# Motor_Slave_2.net
KiCad netlist of a schematic drawn in EAGLE
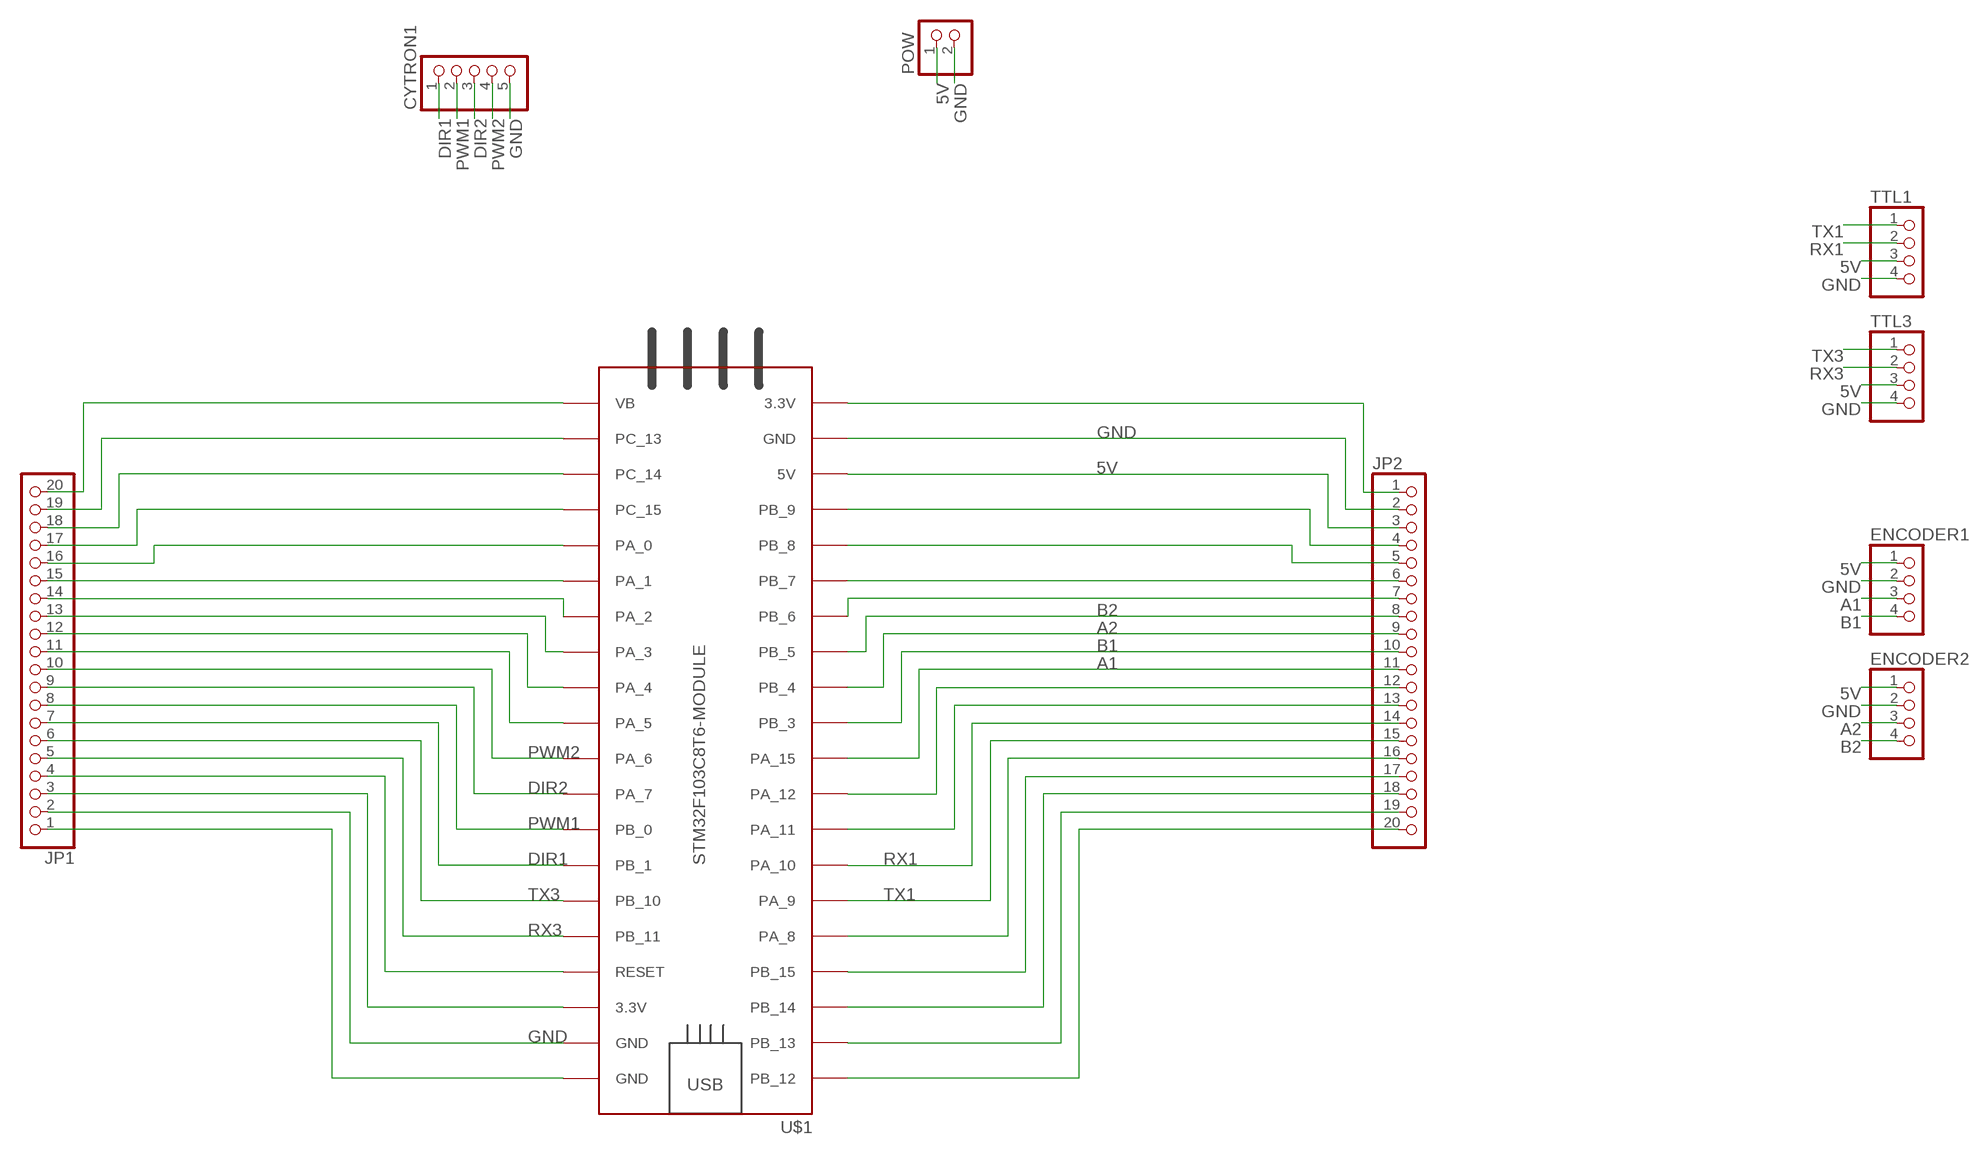
[diagram p0: schematic, sheet 1]

(export (version "E")
  (design (tool "Eeschema 10.0.6"))
  (components
    (comp (ref "CYTRON1")
      (value "PINHD-5_DATA")
      (footprint "eagle-import:1X05_DATA")
      (libsource (lib "eagle-import") (part "PINHD-5_DATA"))
    )
    (comp (ref "ENCODER1")
      (value "PINHD-4_DATA")
      (footprint "eagle-import:1X04_DATA")
      (libsource (lib "eagle-import") (part "PINHD-4_DATA"))
    )
    (comp (ref "ENCODER2")
      (value "PINHD-4_DATA")
      (footprint "eagle-import:1X04_DATA")
      (libsource (lib "eagle-import") (part "PINHD-4_DATA"))
    )
    (comp (ref "JP1")
      (value "PINHD-1X20")
      (footprint "eagle-import:1X20")
      (libsource (lib "eagle-import") (part "PINHD-1X20"))
    )
    (comp (ref "JP2")
      (value "PINHD-1X20")
      (footprint "eagle-import:1X20")
      (libsource (lib "eagle-import") (part "PINHD-1X20"))
    )
    (comp (ref "POW")
      (value "PINHD-2_DATA")
      (footprint "eagle-import:1X02_DATA")
      (libsource (lib "eagle-import") (part "PINHD-2_DATA"))
    )
    (comp (ref "TTL1")
      (value "PINHD-4_DATA")
      (footprint "eagle-import:1X04_DATA")
      (libsource (lib "eagle-import") (part "PINHD-4_DATA"))
    )
    (comp (ref "TTL3")
      (value "PINHD-4_DATA")
      (footprint "eagle-import:1X04_DATA")
      (libsource (lib "eagle-import") (part "PINHD-4_DATA"))
    )
    (comp (ref "U$1")
      (value "STM32F103C8T6-MODULE")
      (footprint "eagle-import:STM32F103C8T6-MODULE")
      (libsource (lib "eagle-import") (part "STM32F103C8T6-MODULE"))
    )
  )
  (nets
    (net (code "1") (name "/5V") (class "Default")
      (node (ref "ENCODER1") (pin "1") (pinfunction "1_1") (pintype "passive"))
      (node (ref "ENCODER2") (pin "1") (pinfunction "1_1") (pintype "passive"))
      (node (ref "JP2") (pin "3") (pinfunction "3_3") (pintype "passive"))
      (node (ref "POW") (pin "1") (pinfunction "1_1") (pintype "passive"))
      (node (ref "TTL1") (pin "3") (pinfunction "3_3") (pintype "passive"))
      (node (ref "TTL3") (pin "3") (pinfunction "3_3") (pintype "passive"))
      (node (ref "U$1") (pin "5V") (pinfunction "5V_5V") (pintype "bidirectional"))
    )
    (net (code "2") (name "/A1") (class "Default")
      (node (ref "ENCODER1") (pin "3") (pinfunction "3_3") (pintype "passive"))
      (node (ref "JP2") (pin "11") (pinfunction "11_11") (pintype "passive"))
      (node (ref "U$1") (pin "PA_15") (pinfunction "PA_15_PA_15") (pintype "bidirectional"))
    )
    (net (code "3") (name "/A2") (class "Default")
      (node (ref "ENCODER2") (pin "3") (pinfunction "3_3") (pintype "passive"))
      (node (ref "JP2") (pin "9") (pinfunction "9_9") (pintype "passive"))
      (node (ref "U$1") (pin "PB_4") (pinfunction "PB_4_PB_4") (pintype "bidirectional"))
    )
    (net (code "4") (name "/B1") (class "Default")
      (node (ref "ENCODER1") (pin "4") (pinfunction "4_4") (pintype "passive"))
      (node (ref "JP2") (pin "10") (pinfunction "10_10") (pintype "passive"))
      (node (ref "U$1") (pin "PB_3") (pinfunction "PB_3_PB_3") (pintype "bidirectional"))
    )
    (net (code "5") (name "/B2") (class "Default")
      (node (ref "ENCODER2") (pin "4") (pinfunction "4_4") (pintype "passive"))
      (node (ref "JP2") (pin "8") (pinfunction "8_8") (pintype "passive"))
      (node (ref "U$1") (pin "PB_5") (pinfunction "PB_5_PB_5") (pintype "bidirectional"))
    )
    (net (code "6") (name "/DIR1") (class "Default")
      (node (ref "CYTRON1") (pin "1") (pinfunction "1_1") (pintype "passive"))
      (node (ref "JP1") (pin "7") (pinfunction "7_7") (pintype "passive"))
      (node (ref "U$1") (pin "PB_1") (pinfunction "PB_1_PB_1") (pintype "bidirectional"))
    )
    (net (code "7") (name "/DIR2") (class "Default")
      (node (ref "CYTRON1") (pin "3") (pinfunction "3_3") (pintype "passive"))
      (node (ref "JP1") (pin "9") (pinfunction "9_9") (pintype "passive"))
      (node (ref "U$1") (pin "PA_7") (pinfunction "PA_7_PA_7") (pintype "bidirectional"))
    )
    (net (code "8") (name "/GND") (class "Default")
      (node (ref "CYTRON1") (pin "5") (pinfunction "5_5") (pintype "passive"))
      (node (ref "ENCODER1") (pin "2") (pinfunction "2_2") (pintype "passive"))
      (node (ref "ENCODER2") (pin "2") (pinfunction "2_2") (pintype "passive"))
      (node (ref "JP1") (pin "2") (pinfunction "2_2") (pintype "passive"))
      (node (ref "JP2") (pin "2") (pinfunction "2_2") (pintype "passive"))
      (node (ref "POW") (pin "2") (pinfunction "2_2") (pintype "passive"))
      (node (ref "TTL1") (pin "4") (pinfunction "4_4") (pintype "passive"))
      (node (ref "TTL3") (pin "4") (pinfunction "4_4") (pintype "passive"))
      (node (ref "U$1") (pin "GND_1") (pinfunction "GND_GND_1") (pintype "bidirectional"))
      (node (ref "U$1") (pin "GND_2") (pinfunction "GND_GND_2") (pintype "bidirectional"))
    )
    (net (code "9") (name "/PWM1") (class "Default")
      (node (ref "CYTRON1") (pin "2") (pinfunction "2_2") (pintype "passive"))
      (node (ref "JP1") (pin "8") (pinfunction "8_8") (pintype "passive"))
      (node (ref "U$1") (pin "PB_0") (pinfunction "PB_0_PB_0") (pintype "bidirectional"))
    )
    (net (code "10") (name "/PWM2") (class "Default")
      (node (ref "CYTRON1") (pin "4") (pinfunction "4_4") (pintype "passive"))
      (node (ref "JP1") (pin "10") (pinfunction "10_10") (pintype "passive"))
      (node (ref "U$1") (pin "PA_6") (pinfunction "PA_6_PA_6") (pintype "bidirectional"))
    )
    (net (code "11") (name "/RX1") (class "Default")
      (node (ref "JP2") (pin "14") (pinfunction "14_14") (pintype "passive"))
      (node (ref "TTL1") (pin "2") (pinfunction "2_2") (pintype "passive"))
      (node (ref "U$1") (pin "PA_10") (pinfunction "PA_10_PA_10") (pintype "bidirectional"))
    )
    (net (code "12") (name "/RX3") (class "Default")
      (node (ref "JP1") (pin "5") (pinfunction "5_5") (pintype "passive"))
      (node (ref "TTL3") (pin "2") (pinfunction "2_2") (pintype "passive"))
      (node (ref "U$1") (pin "PB_11") (pinfunction "PB_11_PB_11") (pintype "bidirectional"))
    )
    (net (code "13") (name "/TX1") (class "Default")
      (node (ref "JP2") (pin "15") (pinfunction "15_15") (pintype "passive"))
      (node (ref "TTL1") (pin "1") (pinfunction "1_1") (pintype "passive"))
      (node (ref "U$1") (pin "PA_9") (pinfunction "PA_9_PA_9") (pintype "bidirectional"))
    )
    (net (code "14") (name "/TX3") (class "Default")
      (node (ref "JP1") (pin "6") (pinfunction "6_6") (pintype "passive"))
      (node (ref "TTL3") (pin "1") (pinfunction "1_1") (pintype "passive"))
      (node (ref "U$1") (pin "PB_10") (pinfunction "PB_10_PB_10") (pintype "bidirectional"))
    )
    (net (code "15") (name "Net-(JP1-Pad1)") (class "Default")
      (node (ref "JP1") (pin "1") (pinfunction "1_1") (pintype "passive"))
      (node (ref "U$1") (pin "GND_3") (pinfunction "GND_GND_3") (pintype "power_in"))
    )
    (net (code "16") (name "Net-(JP1-Pad3)") (class "Default")
      (node (ref "JP1") (pin "3") (pinfunction "3_3") (pintype "passive"))
      (node (ref "U$1") (pin "3.3V_2") (pinfunction "3.3V_3.3V_2") (pintype "bidirectional"))
    )
    (net (code "17") (name "Net-(JP1-Pad4)") (class "Default")
      (node (ref "JP1") (pin "4") (pinfunction "4_4") (pintype "passive"))
      (node (ref "U$1") (pin "RESET") (pinfunction "RESET_RESET") (pintype "bidirectional"))
    )
    (net (code "18") (name "Net-(JP1-Pad11)") (class "Default")
      (node (ref "JP1") (pin "11") (pinfunction "11_11") (pintype "passive"))
      (node (ref "U$1") (pin "PA_5") (pinfunction "PA_5_PA_5") (pintype "bidirectional"))
    )
    (net (code "19") (name "Net-(JP1-Pad12)") (class "Default")
      (node (ref "JP1") (pin "12") (pinfunction "12_12") (pintype "passive"))
      (node (ref "U$1") (pin "PA_4") (pinfunction "PA_4_PA_4") (pintype "bidirectional"))
    )
    (net (code "20") (name "Net-(JP1-Pad13)") (class "Default")
      (node (ref "JP1") (pin "13") (pinfunction "13_13") (pintype "passive"))
      (node (ref "U$1") (pin "PA_3") (pinfunction "PA_3_PA_3") (pintype "bidirectional"))
    )
    (net (code "21") (name "Net-(JP1-Pad14)") (class "Default")
      (node (ref "JP1") (pin "14") (pinfunction "14_14") (pintype "passive"))
      (node (ref "U$1") (pin "PA_2") (pinfunction "PA_2_PA_2") (pintype "bidirectional"))
    )
    (net (code "22") (name "Net-(JP1-Pad15)") (class "Default")
      (node (ref "JP1") (pin "15") (pinfunction "15_15") (pintype "passive"))
      (node (ref "U$1") (pin "PA_1") (pinfunction "PA_1_PA_1") (pintype "bidirectional"))
    )
    (net (code "23") (name "Net-(JP1-Pad16)") (class "Default")
      (node (ref "JP1") (pin "16") (pinfunction "16_16") (pintype "passive"))
      (node (ref "U$1") (pin "PA_0") (pinfunction "PA_0_PA_0") (pintype "bidirectional"))
    )
    (net (code "24") (name "Net-(JP1-Pad17)") (class "Default")
      (node (ref "JP1") (pin "17") (pinfunction "17_17") (pintype "passive"))
      (node (ref "U$1") (pin "PC_15") (pinfunction "PC_15_PC_15") (pintype "bidirectional"))
    )
    (net (code "25") (name "Net-(JP1-Pad18)") (class "Default")
      (node (ref "JP1") (pin "18") (pinfunction "18_18") (pintype "passive"))
      (node (ref "U$1") (pin "PC_14") (pinfunction "PC_14_PC_14") (pintype "bidirectional"))
    )
    (net (code "26") (name "Net-(JP1-Pad19)") (class "Default")
      (node (ref "JP1") (pin "19") (pinfunction "19_19") (pintype "passive"))
      (node (ref "U$1") (pin "PC_13") (pinfunction "PC_13_PC_13") (pintype "bidirectional"))
    )
    (net (code "27") (name "Net-(JP1-Pad20)") (class "Default")
      (node (ref "JP1") (pin "20") (pinfunction "20_20") (pintype "passive"))
      (node (ref "U$1") (pin "VB") (pinfunction "VB_VB") (pintype "bidirectional"))
    )
    (net (code "28") (name "Net-(JP2-Pad1)") (class "Default")
      (node (ref "JP2") (pin "1") (pinfunction "1_1") (pintype "passive"))
      (node (ref "U$1") (pin "3.3V_1") (pinfunction "3.3V_3.3V_1") (pintype "bidirectional"))
    )
    (net (code "29") (name "Net-(JP2-Pad4)") (class "Default")
      (node (ref "JP2") (pin "4") (pinfunction "4_4") (pintype "passive"))
      (node (ref "U$1") (pin "PB_9") (pinfunction "PB_9_PB_9") (pintype "bidirectional"))
    )
    (net (code "30") (name "Net-(JP2-Pad5)") (class "Default")
      (node (ref "JP2") (pin "5") (pinfunction "5_5") (pintype "passive"))
      (node (ref "U$1") (pin "PB_8") (pinfunction "PB_8_PB_8") (pintype "bidirectional"))
    )
    (net (code "31") (name "Net-(JP2-Pad6)") (class "Default")
      (node (ref "JP2") (pin "6") (pinfunction "6_6") (pintype "passive"))
      (node (ref "U$1") (pin "PB_7") (pinfunction "PB_7_PB_7") (pintype "bidirectional"))
    )
    (net (code "32") (name "Net-(JP2-Pad7)") (class "Default")
      (node (ref "JP2") (pin "7") (pinfunction "7_7") (pintype "passive"))
      (node (ref "U$1") (pin "PB_6") (pinfunction "PB_6_PB_6") (pintype "bidirectional"))
    )
    (net (code "33") (name "Net-(JP2-Pad12)") (class "Default")
      (node (ref "JP2") (pin "12") (pinfunction "12_12") (pintype "passive"))
      (node (ref "U$1") (pin "PA_12") (pinfunction "PA_12_PA_12") (pintype "bidirectional"))
    )
    (net (code "34") (name "Net-(JP2-Pad13)") (class "Default")
      (node (ref "JP2") (pin "13") (pinfunction "13_13") (pintype "passive"))
      (node (ref "U$1") (pin "PA_11") (pinfunction "PA_11_PA_11") (pintype "bidirectional"))
    )
    (net (code "35") (name "Net-(JP2-Pad16)") (class "Default")
      (node (ref "JP2") (pin "16") (pinfunction "16_16") (pintype "passive"))
      (node (ref "U$1") (pin "PA_8") (pinfunction "PA_8_PA_8") (pintype "bidirectional"))
    )
    (net (code "36") (name "Net-(JP2-Pad17)") (class "Default")
      (node (ref "JP2") (pin "17") (pinfunction "17_17") (pintype "passive"))
      (node (ref "U$1") (pin "PB_15") (pinfunction "PB_15_PB_15") (pintype "bidirectional"))
    )
    (net (code "37") (name "Net-(JP2-Pad18)") (class "Default")
      (node (ref "JP2") (pin "18") (pinfunction "18_18") (pintype "passive"))
      (node (ref "U$1") (pin "PB_14") (pinfunction "PB_14_PB_14") (pintype "bidirectional"))
    )
    (net (code "38") (name "Net-(JP2-Pad19)") (class "Default")
      (node (ref "JP2") (pin "19") (pinfunction "19_19") (pintype "passive"))
      (node (ref "U$1") (pin "PB_13") (pinfunction "PB_13_PB_13") (pintype "bidirectional"))
    )
    (net (code "39") (name "Net-(JP2-Pad20)") (class "Default")
      (node (ref "JP2") (pin "20") (pinfunction "20_20") (pintype "passive"))
      (node (ref "U$1") (pin "PB_12") (pinfunction "PB_12_PB_12") (pintype "bidirectional"))
    )
  )
)
